# Battery_Board_v3.net
KiCad netlist of a schematic drawn in EAGLE
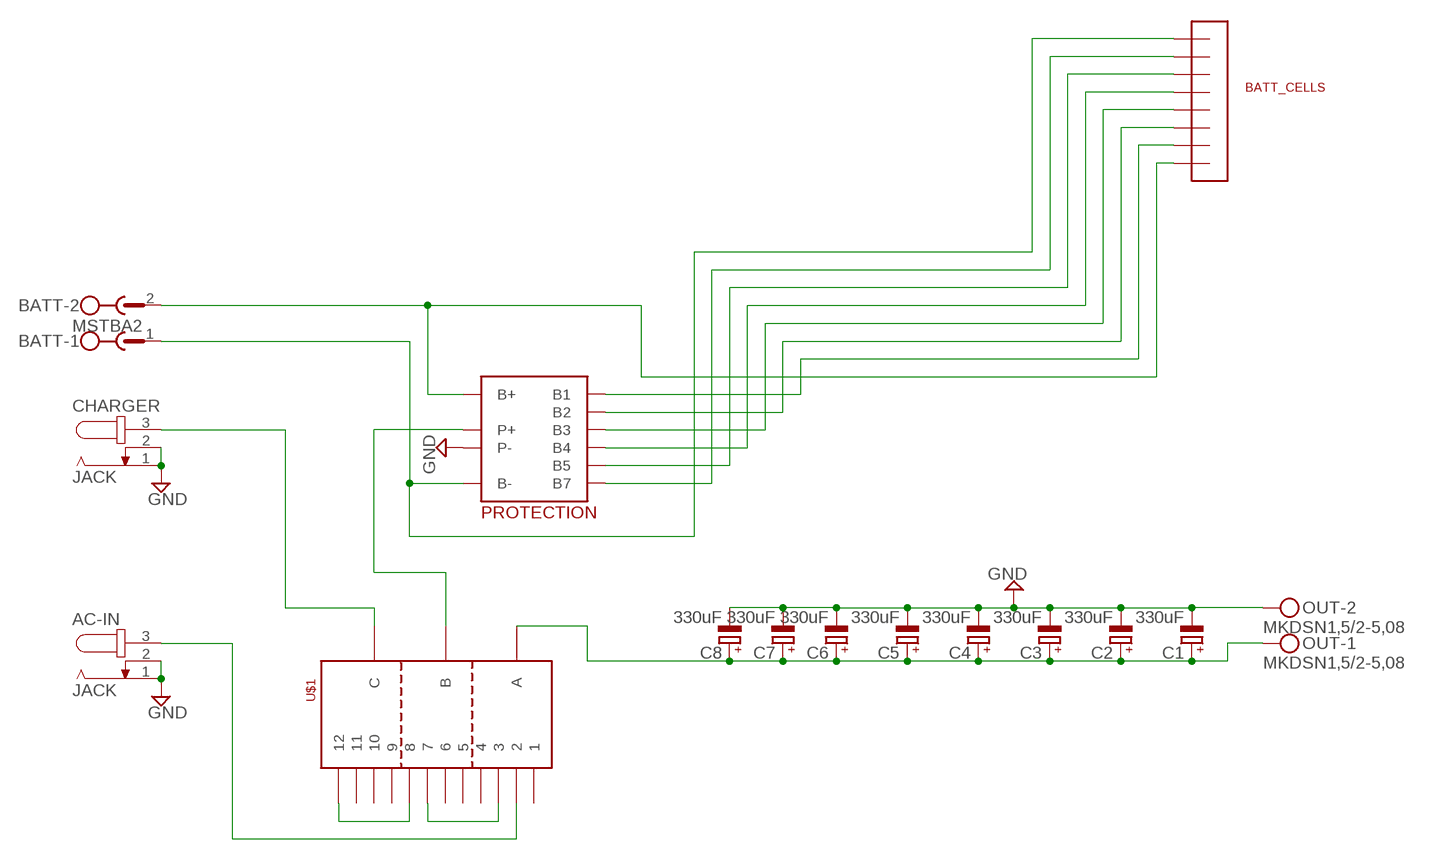
[diagram p0: schematic, sheet 1]

(export (version "E")
  (design (tool "Eeschema 10.0.6"))
  (components
    (comp (ref "AC-IN")
      (value "JACK")
      (footprint "eagle-import:JACK")
      (libsource (lib "eagle-import") (part "JACK"))
    )
    (comp (ref "BATT")
      (value "MSTBA2")
      (footprint "eagle-import:MSTBA2")
      (fields (field (name "MF") "FARNELL") (field (name "MPN") "1757242"))
      (libsource (lib "eagle-import") (part "MSTBA2"))
    )
    (comp (ref "BATT_CELLS")
      (value "JST-XH-8")
      (footprint "eagle-import:8PIN-2.5MM")
      (libsource (lib "eagle-import") (part "JST-XH-8"))
    )
    (comp (ref "C1")
      (value "330uF")
      (footprint "eagle-import:E5-10,5")
      (libsource (lib "eagle-import") (part "CPOL-EUE5-10.5"))
    )
    (comp (ref "C2")
      (value "330uF")
      (footprint "eagle-import:E5-10,5")
      (libsource (lib "eagle-import") (part "CPOL-EUE5-10.5"))
    )
    (comp (ref "C3")
      (value "330uF")
      (footprint "eagle-import:E5-10,5")
      (libsource (lib "eagle-import") (part "CPOL-EUE5-10.5"))
    )
    (comp (ref "C4")
      (value "330uF")
      (footprint "eagle-import:E5-10,5")
      (libsource (lib "eagle-import") (part "CPOL-EUE5-10.5"))
    )
    (comp (ref "C5")
      (value "330uF")
      (footprint "eagle-import:E5-10,5")
      (libsource (lib "eagle-import") (part "CPOL-EUE5-10.5"))
    )
    (comp (ref "C6")
      (value "330uF")
      (footprint "eagle-import:E5-10,5")
      (libsource (lib "eagle-import") (part "CPOL-EUE5-10.5"))
    )
    (comp (ref "C7")
      (value "330uF")
      (footprint "eagle-import:E5-10,5")
      (libsource (lib "eagle-import") (part "CPOL-EUE5-10.5"))
    )
    (comp (ref "C8")
      (value "330uF")
      (footprint "eagle-import:E5-10,5")
      (libsource (lib "eagle-import") (part "CPOL-EUE5-10.5"))
    )
    (comp (ref "CHARGER")
      (value "JACK")
      (footprint "eagle-import:JACK")
      (libsource (lib "eagle-import") (part "JACK"))
    )
    (comp (ref "OUT")
      (value "MKDSN1,5/2-5,08")
      (footprint "eagle-import:MKDSN1,5_2-5,08")
      (fields (field (name "MPN") "MKDSN 1,5/2-5.08"))
      (libsource (lib "eagle-import") (part "MKDSN1,5/2-5,08"))
    )
    (comp (ref "PROTECTION")
      (value "BMS-LIFEPO4-7S")
      (footprint "eagle-import:BMS-LIFEPO4-7S")
      (libsource (lib "eagle-import") (part "BMS-LIFEPO4-7S"))
    )
    (comp (ref "U$1")
      (value "CK1026")
      (footprint "eagle-import:CK1026")
      (libsource (lib "eagle-import") (part "CK1026"))
    )
  )
  (nets
    (net (code "1") (name "GND") (class "Default")
      (node (ref "AC-IN") (pin "1") (pinfunction "1_1") (pintype "passive"))
      (node (ref "AC-IN") (pin "2") (pinfunction "2_2") (pintype "passive"))
      (node (ref "C1") (pin "-") (pinfunction "-_-") (pintype "passive"))
      (node (ref "C2") (pin "-") (pinfunction "-_-") (pintype "passive"))
      (node (ref "C3") (pin "-") (pinfunction "-_-") (pintype "passive"))
      (node (ref "C4") (pin "-") (pinfunction "-_-") (pintype "passive"))
      (node (ref "C5") (pin "-") (pinfunction "-_-") (pintype "passive"))
      (node (ref "C6") (pin "-") (pinfunction "-_-") (pintype "passive"))
      (node (ref "C7") (pin "-") (pinfunction "-_-") (pintype "passive"))
      (node (ref "C8") (pin "-") (pinfunction "-_-") (pintype "passive"))
      (node (ref "CHARGER") (pin "1") (pinfunction "1_1") (pintype "passive"))
      (node (ref "CHARGER") (pin "2") (pinfunction "2_2") (pintype "passive"))
      (node (ref "OUT") (pin "2") (pinfunction "KL_2") (pintype "passive"))
      (node (ref "PROTECTION") (pin "P-") (pinfunction "P-_P-") (pintype "bidirectional"))
    )
    (net (code "2") (name "Net-(AC-IN-Pad3)") (class "Default")
      (node (ref "AC-IN") (pin "3") (pinfunction "3_3") (pintype "passive"))
      (node (ref "U$1") (pin "2") (pinfunction "2_2") (pintype "bidirectional"))
    )
    (net (code "3") (name "Net-(BATT-Pad1)") (class "Default")
      (node (ref "BATT") (pin "1") (pinfunction "1_1") (pintype "passive"))
      (node (ref "BATT_CELLS") (pin "P$1") (pinfunction "P$1_P$1") (pintype "bidirectional"))
      (node (ref "PROTECTION") (pin "B-") (pinfunction "B-_B-") (pintype "bidirectional"))
    )
    (net (code "4") (name "Net-(BATTB-1)") (class "Default")
      (node (ref "BATT") (pin "2") (pinfunction "1_2") (pintype "passive"))
      (node (ref "BATT_CELLS") (pin "P$8") (pinfunction "P$8_P$8") (pintype "bidirectional"))
      (node (ref "PROTECTION") (pin "B+") (pinfunction "B+_B+") (pintype "bidirectional"))
    )
    (net (code "5") (name "Net-(BATT_CELLS-PadP$2)") (class "Default")
      (node (ref "BATT_CELLS") (pin "P$2") (pinfunction "P$2_P$2") (pintype "bidirectional"))
      (node (ref "PROTECTION") (pin "B7") (pinfunction "B7_B7") (pintype "bidirectional"))
    )
    (net (code "6") (name "Net-(BATT_CELLS-PadP$3)") (class "Default")
      (node (ref "BATT_CELLS") (pin "P$3") (pinfunction "P$3_P$3") (pintype "bidirectional"))
      (node (ref "PROTECTION") (pin "B5") (pinfunction "B5_B5") (pintype "bidirectional"))
    )
    (net (code "7") (name "Net-(BATT_CELLS-PadP$4)") (class "Default")
      (node (ref "BATT_CELLS") (pin "P$4") (pinfunction "P$4_P$4") (pintype "bidirectional"))
      (node (ref "PROTECTION") (pin "B4") (pinfunction "B4_B4") (pintype "bidirectional"))
    )
    (net (code "8") (name "Net-(BATT_CELLS-PadP$5)") (class "Default")
      (node (ref "BATT_CELLS") (pin "P$5") (pinfunction "P$5_P$5") (pintype "bidirectional"))
      (node (ref "PROTECTION") (pin "B3") (pinfunction "B3_B3") (pintype "bidirectional"))
    )
    (net (code "9") (name "Net-(BATT_CELLS-PadP$6)") (class "Default")
      (node (ref "BATT_CELLS") (pin "P$6") (pinfunction "P$6_P$6") (pintype "bidirectional"))
      (node (ref "PROTECTION") (pin "B2") (pinfunction "B2_B2") (pintype "bidirectional"))
    )
    (net (code "10") (name "Net-(BATT_CELLS-PadP$7)") (class "Default")
      (node (ref "BATT_CELLS") (pin "P$7") (pinfunction "P$7_P$7") (pintype "bidirectional"))
      (node (ref "PROTECTION") (pin "B1") (pinfunction "B1_B1") (pintype "bidirectional"))
    )
    (net (code "11") (name "Net-(CHARGER-Pad3)") (class "Default")
      (node (ref "CHARGER") (pin "3") (pinfunction "3_3") (pintype "passive"))
      (node (ref "U$1") (pin "C") (pinfunction "C_C") (pintype "bidirectional"))
    )
    (net (code "12") (name "Net-(OUTA-KL)") (class "Default")
      (node (ref "C1") (pin "+") (pinfunction "+_+") (pintype "passive"))
      (node (ref "C2") (pin "+") (pinfunction "+_+") (pintype "passive"))
      (node (ref "C3") (pin "+") (pinfunction "+_+") (pintype "passive"))
      (node (ref "C4") (pin "+") (pinfunction "+_+") (pintype "passive"))
      (node (ref "C5") (pin "+") (pinfunction "+_+") (pintype "passive"))
      (node (ref "C6") (pin "+") (pinfunction "+_+") (pintype "passive"))
      (node (ref "C7") (pin "+") (pinfunction "+_+") (pintype "passive"))
      (node (ref "C8") (pin "+") (pinfunction "+_+") (pintype "passive"))
      (node (ref "OUT") (pin "1") (pinfunction "KL_1") (pintype "passive"))
      (node (ref "U$1") (pin "A") (pinfunction "A_A") (pintype "bidirectional"))
    )
    (net (code "13") (name "Net-(PROTECTION-PadP+)") (class "Default")
      (node (ref "PROTECTION") (pin "P+") (pinfunction "P+_P+") (pintype "bidirectional"))
      (node (ref "U$1") (pin "B") (pinfunction "B_B") (pintype "bidirectional"))
    )
    (net (code "14") (name "Net-(U$1-Pad3)") (class "Default")
      (node (ref "U$1") (pin "3") (pinfunction "3_3") (pintype "bidirectional"))
      (node (ref "U$1") (pin "7") (pinfunction "7_7") (pintype "bidirectional"))
    )
    (net (code "15") (name "Net-(U$1-Pad12)") (class "Default")
      (node (ref "U$1") (pin "12") (pinfunction "12_12") (pintype "bidirectional"))
      (node (ref "U$1") (pin "8") (pinfunction "8_8") (pintype "bidirectional"))
    )
    (net (code "16") (name "unconnected-(U$1-Pad1)") (class "Default")
      (node (ref "U$1") (pin "1") (pinfunction "1_1") (pintype "bidirectional"))
    )
    (net (code "17") (name "unconnected-(U$1-Pad4)") (class "Default")
      (node (ref "U$1") (pin "4") (pinfunction "4_4") (pintype "bidirectional"))
    )
    (net (code "18") (name "unconnected-(U$1-Pad5)") (class "Default")
      (node (ref "U$1") (pin "5") (pinfunction "5_5") (pintype "bidirectional"))
    )
    (net (code "19") (name "unconnected-(U$1-Pad6)") (class "Default")
      (node (ref "U$1") (pin "6") (pinfunction "6_6") (pintype "bidirectional"))
    )
    (net (code "20") (name "unconnected-(U$1-Pad9)") (class "Default")
      (node (ref "U$1") (pin "9") (pinfunction "9_9") (pintype "bidirectional"))
    )
    (net (code "21") (name "unconnected-(U$1-Pad10)") (class "Default")
      (node (ref "U$1") (pin "10") (pinfunction "10_10") (pintype "bidirectional"))
    )
    (net (code "22") (name "unconnected-(U$1-Pad11)") (class "Default")
      (node (ref "U$1") (pin "11") (pinfunction "11_11") (pintype "bidirectional"))
    )
  )
)
